# PAYL0002_PC_JTAGInterface.net
KiCad netlist of a schematic drawn in Altium Designer
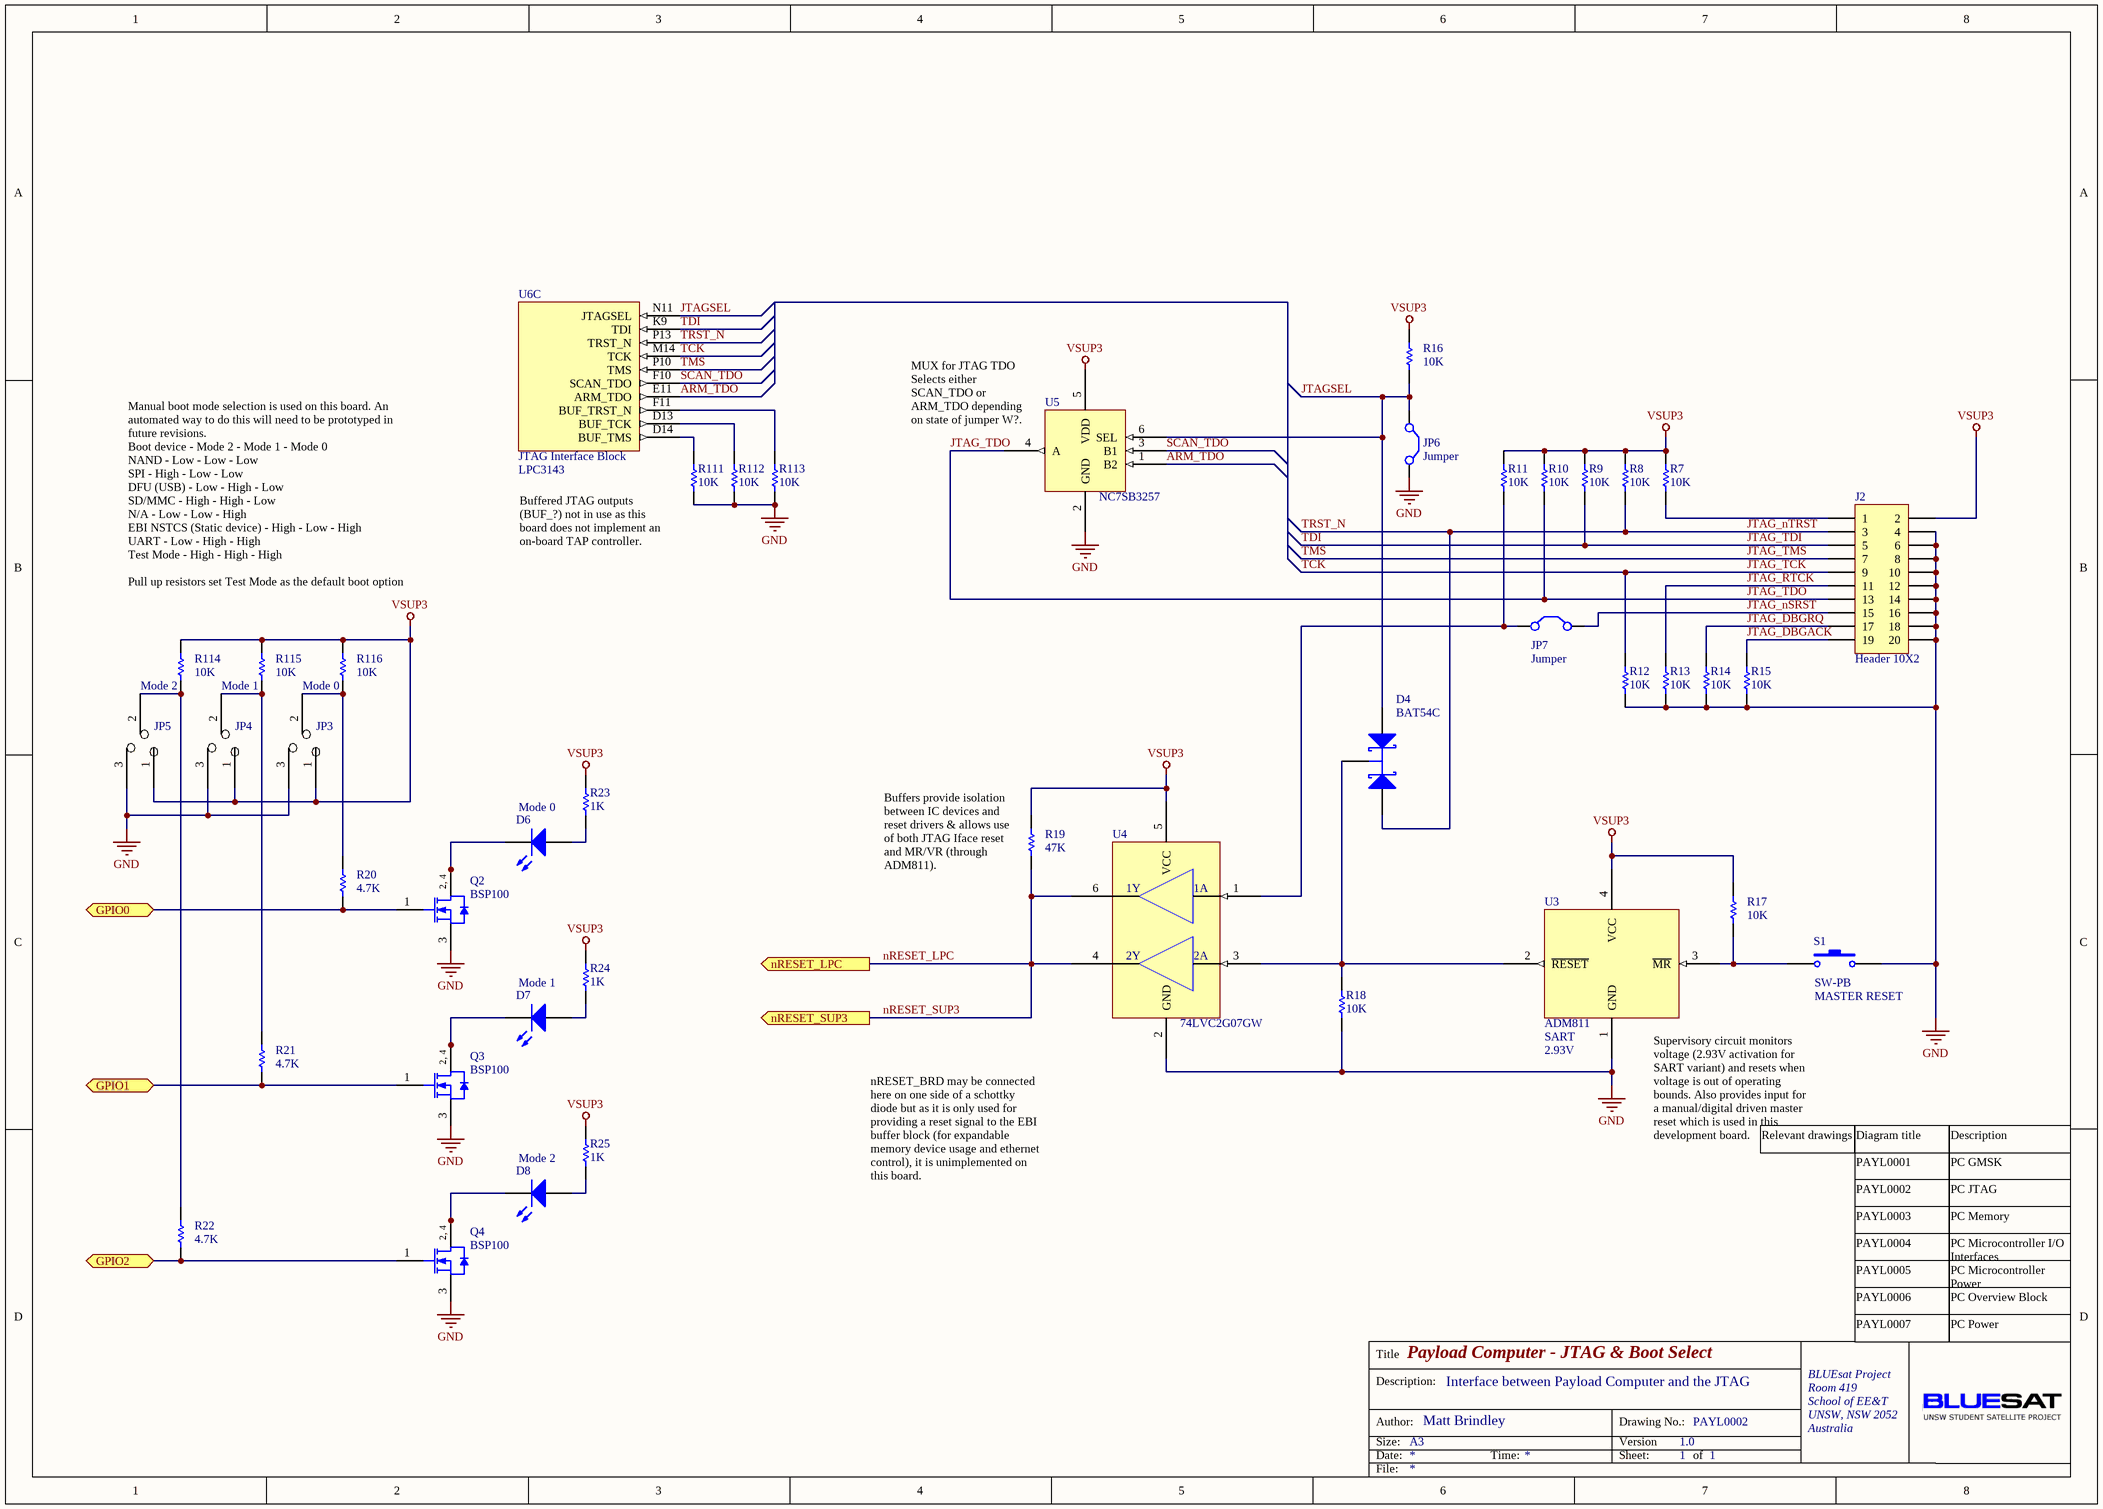
[diagram p0: PAYL0002_PC_JTAGInterface.SchDoc]

(export (version "E")
  (design (tool "Eeschema 10.0.6"))
  (components
    (comp (ref "D4")
      (value "BAT54C")
      (footprint "SOT23_N")
      (description "Schottky Barrier Double Diode")
      (fields (field (name "PUBLISHER") "Altium Limited"))
      (libsource (lib "Philips Discrete Diode - Schottky") (part "BAT54C"))
    )
    (comp (ref "D6")
      (value "LED2")
      (footprint "DSO-F2/D6.1")
      (description "Typical RED, GREEN, YELLOW, AMBER GaAs LED")
      (fields (field (name "PUBLISHER") "Altium Limited"))
      (libsource (lib "Miscellaneous Devices") (part "LED2"))
    )
    (comp (ref "D7")
      (value "LED2")
      (footprint "DSO-F2/D6.1")
      (description "Typical RED, GREEN, YELLOW, AMBER GaAs LED")
      (fields (field (name "PUBLISHER") "Altium Limited"))
      (libsource (lib "Miscellaneous Devices") (part "LED2"))
    )
    (comp (ref "D8")
      (value "LED2")
      (footprint "DSO-F2/D6.1")
      (description "Typical RED, GREEN, YELLOW, AMBER GaAs LED")
      (fields (field (name "PUBLISHER") "Altium Limited"))
      (libsource (lib "Miscellaneous Devices") (part "LED2"))
    )
    (comp (ref "J2")
      (value "Header 10X2")
      (footprint "HDR2X10")
      (description "Header, 10-Pin, Dual row")
      (fields (field (name "PUBLISHER") "Altium Limited"))
      (libsource (lib "Miscellaneous Connectors") (part "Header 10X2"))
    )
    (comp (ref "JP3")
      (value "Jumper")
      (footprint "HDR1X3")
      (description "3 pin jumper for selection")
      (fields (field (name "PUBLISHER") "Altium Limited"))
      (libsource (lib "PC_Components") (part "2 position jumper"))
    )
    (comp (ref "JP4")
      (value "Jumper")
      (footprint "HDR1X3")
      (description "3 pin jumper for selection")
      (fields (field (name "PUBLISHER") "Altium Limited"))
      (libsource (lib "PC_Components") (part "2 position jumper"))
    )
    (comp (ref "JP5")
      (value "Jumper")
      (footprint "HDR1X3")
      (description "3 pin jumper for selection")
      (fields (field (name "PUBLISHER") "Altium Limited"))
      (libsource (lib "PC_Components") (part "2 position jumper"))
    )
    (comp (ref "JP6")
      (value "Jumper")
      (footprint "HDR1X2")
      (description "Jumper Wire")
      (fields (field (name "PUBLISHER") "Altium Limited"))
      (libsource (lib "Miscellaneous Devices") (part "Jumper"))
    )
    (comp (ref "JP7")
      (value "Jumper")
      (footprint "HDR1X2")
      (description "Jumper Wire")
      (fields (field (name "PUBLISHER") "Altium Limited"))
      (libsource (lib "Miscellaneous Devices") (part "Jumper"))
    )
    (comp (ref "Q2")
      (value "BSP100")
      (footprint "SOT223_N")
      (description "N-channel Enhancement Mode MOSFET")
      (fields (field (name "PUBLISHER") "Altium Limited"))
      (libsource (lib "Philips Discrete MOSFET - Power") (part "BSP100"))
    )
    (comp (ref "Q3")
      (value "BSP100")
      (footprint "SOT223_N")
      (description "N-channel Enhancement Mode MOSFET")
      (fields (field (name "PUBLISHER") "Altium Limited"))
      (libsource (lib "Philips Discrete MOSFET - Power") (part "BSP100"))
    )
    (comp (ref "Q4")
      (value "BSP100")
      (footprint "SOT223_N")
      (description "N-channel Enhancement Mode MOSFET")
      (fields (field (name "PUBLISHER") "Altium Limited"))
      (libsource (lib "Philips Discrete MOSFET - Power") (part "BSP100"))
    )
    (comp (ref "R7")
      (value "10K")
      (footprint "6-0805_L")
      (description "Semiconductor Resistor")
      (fields (field (name "Comment") "Res Semi") (field (name "PUBLISHER") "Altium Limited"))
      (libsource (lib "Miscellaneous Devices") (part "Res Semi"))
    )
    (comp (ref "R8")
      (value "10K")
      (footprint "6-0805_L")
      (description "Semiconductor Resistor")
      (fields (field (name "Comment") "Res Semi") (field (name "PUBLISHER") "Altium Limited"))
      (libsource (lib "Miscellaneous Devices") (part "Res Semi"))
    )
    (comp (ref "R9")
      (value "10K")
      (footprint "6-0805_L")
      (description "Semiconductor Resistor")
      (fields (field (name "Comment") "Res Semi") (field (name "PUBLISHER") "Altium Limited"))
      (libsource (lib "Miscellaneous Devices") (part "Res Semi"))
    )
    (comp (ref "R10")
      (value "10K")
      (footprint "6-0805_L")
      (description "Semiconductor Resistor")
      (fields (field (name "Comment") "Res Semi") (field (name "PUBLISHER") "Altium Limited"))
      (libsource (lib "Miscellaneous Devices") (part "Res Semi"))
    )
    (comp (ref "R11")
      (value "10K")
      (footprint "6-0805_L")
      (description "Semiconductor Resistor")
      (fields (field (name "Comment") "Res Semi") (field (name "PUBLISHER") "Altium Limited"))
      (libsource (lib "Miscellaneous Devices") (part "Res Semi"))
    )
    (comp (ref "R12")
      (value "10K")
      (footprint "6-0805_L")
      (description "Semiconductor Resistor")
      (fields (field (name "Comment") "Res Semi") (field (name "PUBLISHER") "Altium Limited"))
      (libsource (lib "Miscellaneous Devices") (part "Res Semi"))
    )
    (comp (ref "R13")
      (value "10K")
      (footprint "6-0805_L")
      (description "Semiconductor Resistor")
      (fields (field (name "Comment") "Res Semi") (field (name "PUBLISHER") "Altium Limited"))
      (libsource (lib "Miscellaneous Devices") (part "Res Semi"))
    )
    (comp (ref "R14")
      (value "10K")
      (footprint "6-0805_L")
      (description "Semiconductor Resistor")
      (fields (field (name "Comment") "Res Semi") (field (name "PUBLISHER") "Altium Limited"))
      (libsource (lib "Miscellaneous Devices") (part "Res Semi"))
    )
    (comp (ref "R15")
      (value "10K")
      (footprint "6-0805_L")
      (description "Semiconductor Resistor")
      (fields (field (name "Comment") "Res Semi") (field (name "PUBLISHER") "Altium Limited"))
      (libsource (lib "Miscellaneous Devices") (part "Res Semi"))
    )
    (comp (ref "R16")
      (value "10K")
      (footprint "6-0805_L")
      (description "Semiconductor Resistor")
      (fields (field (name "Comment") "Res Semi") (field (name "PUBLISHER") "Altium Limited"))
      (libsource (lib "Miscellaneous Devices") (part "Res Semi"))
    )
    (comp (ref "R17")
      (value "10K")
      (footprint "6-0805_L")
      (description "Semiconductor Resistor")
      (fields (field (name "Comment") "Res Semi") (field (name "PUBLISHER") "Altium Limited"))
      (libsource (lib "Miscellaneous Devices") (part "Res Semi"))
    )
    (comp (ref "R18")
      (value "10K")
      (footprint "6-0805_L")
      (description "Semiconductor Resistor")
      (fields (field (name "Comment") "Res Semi") (field (name "PUBLISHER") "Altium Limited"))
      (libsource (lib "Miscellaneous Devices") (part "Res Semi"))
    )
    (comp (ref "R19")
      (value "47K")
      (footprint "6-0805_L")
      (description "Semiconductor Resistor")
      (fields (field (name "Comment") "Res Semi") (field (name "PUBLISHER") "Altium Limited"))
      (libsource (lib "Miscellaneous Devices") (part "Res Semi"))
    )
    (comp (ref "R20")
      (value "4.7K")
      (footprint "6-0805_L")
      (description "Semiconductor Resistor")
      (fields (field (name "Comment") "Res Semi") (field (name "PUBLISHER") "Altium Limited"))
      (libsource (lib "Miscellaneous Devices") (part "Res Semi"))
    )
    (comp (ref "R21")
      (value "4.7K")
      (footprint "6-0805_L")
      (description "Semiconductor Resistor")
      (fields (field (name "Comment") "Res Semi") (field (name "PUBLISHER") "Altium Limited"))
      (libsource (lib "Miscellaneous Devices") (part "Res Semi"))
    )
    (comp (ref "R22")
      (value "4.7K")
      (footprint "6-0805_L")
      (description "Semiconductor Resistor")
      (fields (field (name "Comment") "Res Semi") (field (name "PUBLISHER") "Altium Limited"))
      (libsource (lib "Miscellaneous Devices") (part "Res Semi"))
    )
    (comp (ref "R23")
      (value "1K")
      (footprint "6-0805_L")
      (description "Semiconductor Resistor")
      (fields (field (name "Comment") "Res Semi") (field (name "PUBLISHER") "Altium Limited"))
      (libsource (lib "Miscellaneous Devices") (part "Res Semi"))
    )
    (comp (ref "R24")
      (value "1K")
      (footprint "6-0805_L")
      (description "Semiconductor Resistor")
      (fields (field (name "Comment") "Res Semi") (field (name "PUBLISHER") "Altium Limited"))
      (libsource (lib "Miscellaneous Devices") (part "Res Semi"))
    )
    (comp (ref "R25")
      (value "1K")
      (footprint "6-0805_L")
      (description "Semiconductor Resistor")
      (fields (field (name "Comment") "Res Semi") (field (name "PUBLISHER") "Altium Limited"))
      (libsource (lib "Miscellaneous Devices") (part "Res Semi"))
    )
    (comp (ref "R111")
      (value "10K")
      (footprint "6-0805_L")
      (description "Semiconductor Resistor")
      (fields (field (name "Comment") "Res Semi") (field (name "PUBLISHER") "Altium Limited"))
      (libsource (lib "Miscellaneous Devices") (part "Res Semi"))
    )
    (comp (ref "R112")
      (value "10K")
      (footprint "6-0805_L")
      (description "Semiconductor Resistor")
      (fields (field (name "Comment") "Res Semi") (field (name "PUBLISHER") "Altium Limited"))
      (libsource (lib "Miscellaneous Devices") (part "Res Semi"))
    )
    (comp (ref "R113")
      (value "10K")
      (footprint "6-0805_L")
      (description "Semiconductor Resistor")
      (fields (field (name "Comment") "Res Semi") (field (name "PUBLISHER") "Altium Limited"))
      (libsource (lib "Miscellaneous Devices") (part "Res Semi"))
    )
    (comp (ref "R114")
      (value "10K")
      (footprint "6-0805_L")
      (description "Semiconductor Resistor")
      (fields (field (name "Comment") "Res Semi") (field (name "PUBLISHER") "Altium Limited"))
      (libsource (lib "Miscellaneous Devices") (part "Res Semi"))
    )
    (comp (ref "R115")
      (value "10K")
      (footprint "6-0805_L")
      (description "Semiconductor Resistor")
      (fields (field (name "Comment") "Res Semi") (field (name "PUBLISHER") "Altium Limited"))
      (libsource (lib "Miscellaneous Devices") (part "Res Semi"))
    )
    (comp (ref "R116")
      (value "10K")
      (footprint "6-0805_L")
      (description "Semiconductor Resistor")
      (fields (field (name "Comment") "Res Semi") (field (name "PUBLISHER") "Altium Limited"))
      (libsource (lib "Miscellaneous Devices") (part "Res Semi"))
    )
    (comp (ref "S1")
      (value "SW-PB")
      (footprint "SPST-2")
      (description "Switch")
      (fields (field (name "PUBLISHER") "Altium Limited"))
      (libsource (lib "Miscellaneous Devices") (part "SW-PB"))
    )
    (comp (ref "U3")
      (value "ADM811")
      (footprint "SOT190P230X102-4N")
      (description "Supervisory Circuit")
      (fields (field (name "PUBLISHER") "Altium Limited"))
      (libsource (lib "PC_Components") (part "ADM811"))
    )
    (comp (ref "U4")
      (value "74LVC2G07GW")
      (footprint "SOT65P210X110-6M")
      (description "Non-inverting buffers with open-drain outputs")
      (fields (field (name "PUBLISHER") "Altium Limited"))
      (libsource (lib "PC_Components") (part "74LVC2G07GW"))
    )
    (comp (ref "U5")
      (value "NC7SB3257")
      (footprint "TSOP65P210X110-6N")
      (description "2:1 Mux, Fairchild")
      (fields (field (name "PUBLISHER") "Altium Limited"))
      (libsource (lib "PC_Components") (part "NC7SB3257"))
    )
    (comp (ref "U6")
      (value "LPC3143")
      (footprint "PC_Footprints:BGA180C80P14X14_1200X1200X120")
      (description "NXP ARM9 based microcontroller")
      (fields (field (name "PUBLISHER") "BLUEsat Project"))
      (libsource (lib "PC_Components") (part "LPC3143"))
    )
  )
  (nets
    (net (code "1") (name "/ARM_TDO") (class "Default")
      (node (ref "U5") (pin "1") (pinfunction "B2_1") (pintype "input"))
      (node (ref "U6") (pin "E11") (pinfunction "ARM_TDO_E11") (pintype "output"))
    )
    (net (code "2") (name "/GPIO0") (class "Default")
      (node (ref "Q2") (pin "1") (pinfunction "G_1") (pintype "passive"))
      (node (ref "R20") (pin "1") (pinfunction "1_1") (pintype "passive"))
    )
    (net (code "3") (name "/GPIO1") (class "Default")
      (node (ref "Q3") (pin "1") (pinfunction "G_1") (pintype "passive"))
      (node (ref "R21") (pin "1") (pinfunction "1_1") (pintype "passive"))
    )
    (net (code "4") (name "/GPIO2") (class "Default")
      (node (ref "Q4") (pin "1") (pinfunction "G_1") (pintype "passive"))
      (node (ref "R22") (pin "1") (pinfunction "1_1") (pintype "passive"))
    )
    (net (code "5") (name "/JTAGSEL") (class "Default")
      (node (ref "D4") (pin "2") (pinfunction "A2_2") (pintype "passive"))
      (node (ref "JP6") (pin "1") (pinfunction "C1_1") (pintype "passive"))
      (node (ref "R16") (pin "1") (pinfunction "1_1") (pintype "passive"))
      (node (ref "U5") (pin "6") (pinfunction "SEL_6") (pintype "input"))
      (node (ref "U6") (pin "N11") (pinfunction "JTAGSEL_N11") (pintype "input"))
    )
    (net (code "6") (name "/JTAG_DBGACK") (class "Default")
      (node (ref "J2") (pin "19") (pinfunction "19_19") (pintype "passive"))
      (node (ref "R15") (pin "2") (pinfunction "2_2") (pintype "passive"))
    )
    (net (code "7") (name "/JTAG_DBGRQ") (class "Default")
      (node (ref "J2") (pin "17") (pinfunction "17_17") (pintype "passive"))
      (node (ref "R14") (pin "2") (pinfunction "2_2") (pintype "passive"))
    )
    (net (code "8") (name "/JTAG_RTCK") (class "Default")
      (node (ref "J2") (pin "11") (pinfunction "11_11") (pintype "passive"))
      (node (ref "R13") (pin "2") (pinfunction "2_2") (pintype "passive"))
    )
    (net (code "9") (name "/JTAG_TCK") (class "Default")
      (node (ref "J2") (pin "9") (pinfunction "9_9") (pintype "passive"))
      (node (ref "R12") (pin "2") (pinfunction "2_2") (pintype "passive"))
      (node (ref "U6") (pin "M14") (pinfunction "TCK_M14") (pintype "input"))
    )
    (net (code "10") (name "/JTAG_TDI") (class "Default")
      (node (ref "J2") (pin "5") (pinfunction "5_5") (pintype "passive"))
      (node (ref "R9") (pin "1") (pinfunction "1_1") (pintype "passive"))
      (node (ref "U6") (pin "K9") (pinfunction "TDI_K9") (pintype "input"))
    )
    (net (code "11") (name "/JTAG_TDO") (class "Default")
      (node (ref "J2") (pin "13") (pinfunction "13_13") (pintype "passive"))
      (node (ref "R10") (pin "1") (pinfunction "1_1") (pintype "passive"))
      (node (ref "U5") (pin "4") (pinfunction "A_4") (pintype "output"))
    )
    (net (code "12") (name "/JTAG_TMS") (class "Default")
      (node (ref "J2") (pin "7") (pinfunction "7_7") (pintype "passive"))
      (node (ref "U6") (pin "P10") (pinfunction "TMS_P10") (pintype "input"))
    )
    (net (code "13") (name "/JTAG_nSRST") (class "Default")
      (node (ref "J2") (pin "15") (pinfunction "15_15") (pintype "passive"))
      (node (ref "JP7") (pin "2") (pinfunction "C2_2") (pintype "passive"))
    )
    (net (code "14") (name "/JTAG_nTRST") (class "Default")
      (node (ref "D4") (pin "1") (pinfunction "A1_1") (pintype "passive"))
      (node (ref "J2") (pin "3") (pinfunction "3_3") (pintype "passive"))
      (node (ref "R8") (pin "1") (pinfunction "1_1") (pintype "passive"))
      (node (ref "U6") (pin "P13") (pinfunction "TRST_N_P13") (pintype "input"))
    )
    (net (code "15") (name "/SCAN_TDO") (class "Default")
      (node (ref "U5") (pin "3") (pinfunction "B1_3") (pintype "input"))
      (node (ref "U6") (pin "F10") (pinfunction "SCAN_TDO_F10") (pintype "output"))
    )
    (net (code "16") (name "/nRESET_LPC") (class "Default")
      (node (ref "R19") (pin "1") (pinfunction "1_1") (pintype "passive"))
      (node (ref "U4") (pin "4") (pinfunction "2Y_4") (pintype "tri_state"))
      (node (ref "U4") (pin "6") (pinfunction "1Y_6") (pintype "tri_state"))
    )
    (net (code "17") (name "GND") (class "Default")
      (node (ref "J2") (pin "10") (pinfunction "10_10") (pintype "passive"))
      (node (ref "J2") (pin "12") (pinfunction "12_12") (pintype "passive"))
      (node (ref "J2") (pin "14") (pinfunction "14_14") (pintype "passive"))
      (node (ref "J2") (pin "16") (pinfunction "16_16") (pintype "passive"))
      (node (ref "J2") (pin "18") (pinfunction "18_18") (pintype "passive"))
      (node (ref "J2") (pin "20") (pinfunction "20_20") (pintype "passive"))
      (node (ref "J2") (pin "4") (pinfunction "4_4") (pintype "passive"))
      (node (ref "J2") (pin "6") (pinfunction "6_6") (pintype "passive"))
      (node (ref "J2") (pin "8") (pinfunction "8_8") (pintype "passive"))
      (node (ref "JP3") (pin "3") (pinfunction "3_3") (pintype "passive"))
      (node (ref "JP4") (pin "3") (pinfunction "3_3") (pintype "passive"))
      (node (ref "JP5") (pin "3") (pinfunction "3_3") (pintype "passive"))
      (node (ref "JP6") (pin "2") (pinfunction "C2_2") (pintype "passive"))
      (node (ref "Q2") (pin "3") (pinfunction "S_3") (pintype "passive"))
      (node (ref "Q3") (pin "3") (pinfunction "S_3") (pintype "passive"))
      (node (ref "Q4") (pin "3") (pinfunction "S_3") (pintype "passive"))
      (node (ref "R111") (pin "1") (pinfunction "1_1") (pintype "passive"))
      (node (ref "R112") (pin "1") (pinfunction "1_1") (pintype "passive"))
      (node (ref "R113") (pin "1") (pinfunction "1_1") (pintype "passive"))
      (node (ref "R12") (pin "1") (pinfunction "1_1") (pintype "passive"))
      (node (ref "R13") (pin "1") (pinfunction "1_1") (pintype "passive"))
      (node (ref "R14") (pin "1") (pinfunction "1_1") (pintype "passive"))
      (node (ref "R15") (pin "1") (pinfunction "1_1") (pintype "passive"))
      (node (ref "R18") (pin "1") (pinfunction "1_1") (pintype "passive"))
      (node (ref "S1") (pin "2") (pinfunction "2_2") (pintype "passive"))
      (node (ref "U3") (pin "1") (pinfunction "GND_1") (pintype "power_in"))
      (node (ref "U4") (pin "2") (pinfunction "GND_2") (pintype "power_in"))
      (node (ref "U5") (pin "2") (pinfunction "GND_2") (pintype "power_in"))
    )
    (net (code "18") (name "Net-(D4-K)") (class "Default")
      (node (ref "D4") (pin "3") (pinfunction "K_3") (pintype "passive"))
      (node (ref "R18") (pin "2") (pinfunction "2_2") (pintype "passive"))
      (node (ref "U3") (pin "2") (pinfunction "~{RESET}_2") (pintype "output"))
      (node (ref "U4") (pin "3") (pinfunction "2A_3") (pintype "input"))
    )
    (net (code "19") (name "Net-(D6-A)") (class "Default")
      (node (ref "D6") (pin "1") (pinfunction "A_1") (pintype "passive"))
      (node (ref "R23") (pin "1") (pinfunction "1_1") (pintype "passive"))
    )
    (net (code "20") (name "Net-(D6-K)") (class "Default")
      (node (ref "D6") (pin "2") (pinfunction "K_2") (pintype "passive"))
      (node (ref "Q2") (pin "2") (pinfunction "D_2") (pintype "passive"))
      (node (ref "Q2") (pin "4") (pinfunction "D_4") (pintype "passive"))
    )
    (net (code "21") (name "Net-(D7-A)") (class "Default")
      (node (ref "D7") (pin "1") (pinfunction "A_1") (pintype "passive"))
      (node (ref "R24") (pin "1") (pinfunction "1_1") (pintype "passive"))
    )
    (net (code "22") (name "Net-(D7-K)") (class "Default")
      (node (ref "D7") (pin "2") (pinfunction "K_2") (pintype "passive"))
      (node (ref "Q3") (pin "2") (pinfunction "D_2") (pintype "passive"))
      (node (ref "Q3") (pin "4") (pinfunction "D_4") (pintype "passive"))
    )
    (net (code "23") (name "Net-(D8-A)") (class "Default")
      (node (ref "D8") (pin "1") (pinfunction "A_1") (pintype "passive"))
      (node (ref "R25") (pin "1") (pinfunction "1_1") (pintype "passive"))
    )
    (net (code "24") (name "Net-(D8-K)") (class "Default")
      (node (ref "D8") (pin "2") (pinfunction "K_2") (pintype "passive"))
      (node (ref "Q4") (pin "2") (pinfunction "D_2") (pintype "passive"))
      (node (ref "Q4") (pin "4") (pinfunction "D_4") (pintype "passive"))
    )
    (net (code "25") (name "Net-(J2-Pad1)") (class "Default")
      (node (ref "J2") (pin "1") (pinfunction "1_1") (pintype "passive"))
      (node (ref "R7") (pin "1") (pinfunction "1_1") (pintype "passive"))
    )
    (net (code "26") (name "Net-(JP3-Pad2)") (class "Default")
      (node (ref "JP3") (pin "2") (pinfunction "2_2") (pintype "passive"))
      (node (ref "R116") (pin "1") (pinfunction "1_1") (pintype "passive"))
      (node (ref "R20") (pin "2") (pinfunction "2_2") (pintype "passive"))
    )
    (net (code "27") (name "Net-(JP4-Pad2)") (class "Default")
      (node (ref "JP4") (pin "2") (pinfunction "2_2") (pintype "passive"))
      (node (ref "R115") (pin "1") (pinfunction "1_1") (pintype "passive"))
      (node (ref "R21") (pin "2") (pinfunction "2_2") (pintype "passive"))
    )
    (net (code "28") (name "Net-(JP5-Pad2)") (class "Default")
      (node (ref "JP5") (pin "2") (pinfunction "2_2") (pintype "passive"))
      (node (ref "R114") (pin "1") (pinfunction "1_1") (pintype "passive"))
      (node (ref "R22") (pin "2") (pinfunction "2_2") (pintype "passive"))
    )
    (net (code "29") (name "Net-(JP7-C1)") (class "Default")
      (node (ref "JP7") (pin "1") (pinfunction "C1_1") (pintype "passive"))
      (node (ref "R11") (pin "1") (pinfunction "1_1") (pintype "passive"))
      (node (ref "U4") (pin "1") (pinfunction "1A_1") (pintype "input"))
    )
    (net (code "30") (name "Net-(U3-~{MR})") (class "Default")
      (node (ref "R17") (pin "1") (pinfunction "1_1") (pintype "passive"))
      (node (ref "S1") (pin "1") (pinfunction "1_1") (pintype "passive"))
      (node (ref "U3") (pin "3") (pinfunction "~{MR}_3") (pintype "input"))
    )
    (net (code "31") (name "Net-(U6C-BUF_TCK)") (class "Default")
      (node (ref "R112") (pin "2") (pinfunction "2_2") (pintype "passive"))
      (node (ref "U6") (pin "D13") (pinfunction "BUF_TCK_D13") (pintype "output"))
    )
    (net (code "32") (name "Net-(U6C-BUF_TMS)") (class "Default")
      (node (ref "R111") (pin "2") (pinfunction "2_2") (pintype "passive"))
      (node (ref "U6") (pin "D14") (pinfunction "BUF_TMS_D14") (pintype "output"))
    )
    (net (code "33") (name "Net-(U6C-BUF_TRST_N)") (class "Default")
      (node (ref "R113") (pin "2") (pinfunction "2_2") (pintype "passive"))
      (node (ref "U6") (pin "F11") (pinfunction "BUF_TRST_N_F11") (pintype "output"))
    )
    (net (code "34") (name "VSUP3") (class "Default")
      (node (ref "J2") (pin "2") (pinfunction "2_2") (pintype "passive"))
      (node (ref "JP3") (pin "1") (pinfunction "1_1") (pintype "passive"))
      (node (ref "JP4") (pin "1") (pinfunction "1_1") (pintype "passive"))
      (node (ref "JP5") (pin "1") (pinfunction "1_1") (pintype "passive"))
      (node (ref "R10") (pin "2") (pinfunction "2_2") (pintype "passive"))
      (node (ref "R11") (pin "2") (pinfunction "2_2") (pintype "passive"))
      (node (ref "R114") (pin "2") (pinfunction "2_2") (pintype "passive"))
      (node (ref "R115") (pin "2") (pinfunction "2_2") (pintype "passive"))
      (node (ref "R116") (pin "2") (pinfunction "2_2") (pintype "passive"))
      (node (ref "R16") (pin "2") (pinfunction "2_2") (pintype "passive"))
      (node (ref "R17") (pin "2") (pinfunction "2_2") (pintype "passive"))
      (node (ref "R19") (pin "2") (pinfunction "2_2") (pintype "passive"))
      (node (ref "R23") (pin "2") (pinfunction "2_2") (pintype "passive"))
      (node (ref "R24") (pin "2") (pinfunction "2_2") (pintype "passive"))
      (node (ref "R25") (pin "2") (pinfunction "2_2") (pintype "passive"))
      (node (ref "R7") (pin "2") (pinfunction "2_2") (pintype "passive"))
      (node (ref "R8") (pin "2") (pinfunction "2_2") (pintype "passive"))
      (node (ref "R9") (pin "2") (pinfunction "2_2") (pintype "passive"))
      (node (ref "U3") (pin "4") (pinfunction "VCC_4") (pintype "power_in"))
      (node (ref "U4") (pin "5") (pinfunction "VCC_5") (pintype "power_in"))
      (node (ref "U5") (pin "5") (pinfunction "VDD_5") (pintype "power_in"))
    )
  )
)
